# 1-Schematic_Bluetonium_canister.net
KiCad netlist of a schematic drawn in EasyEDA
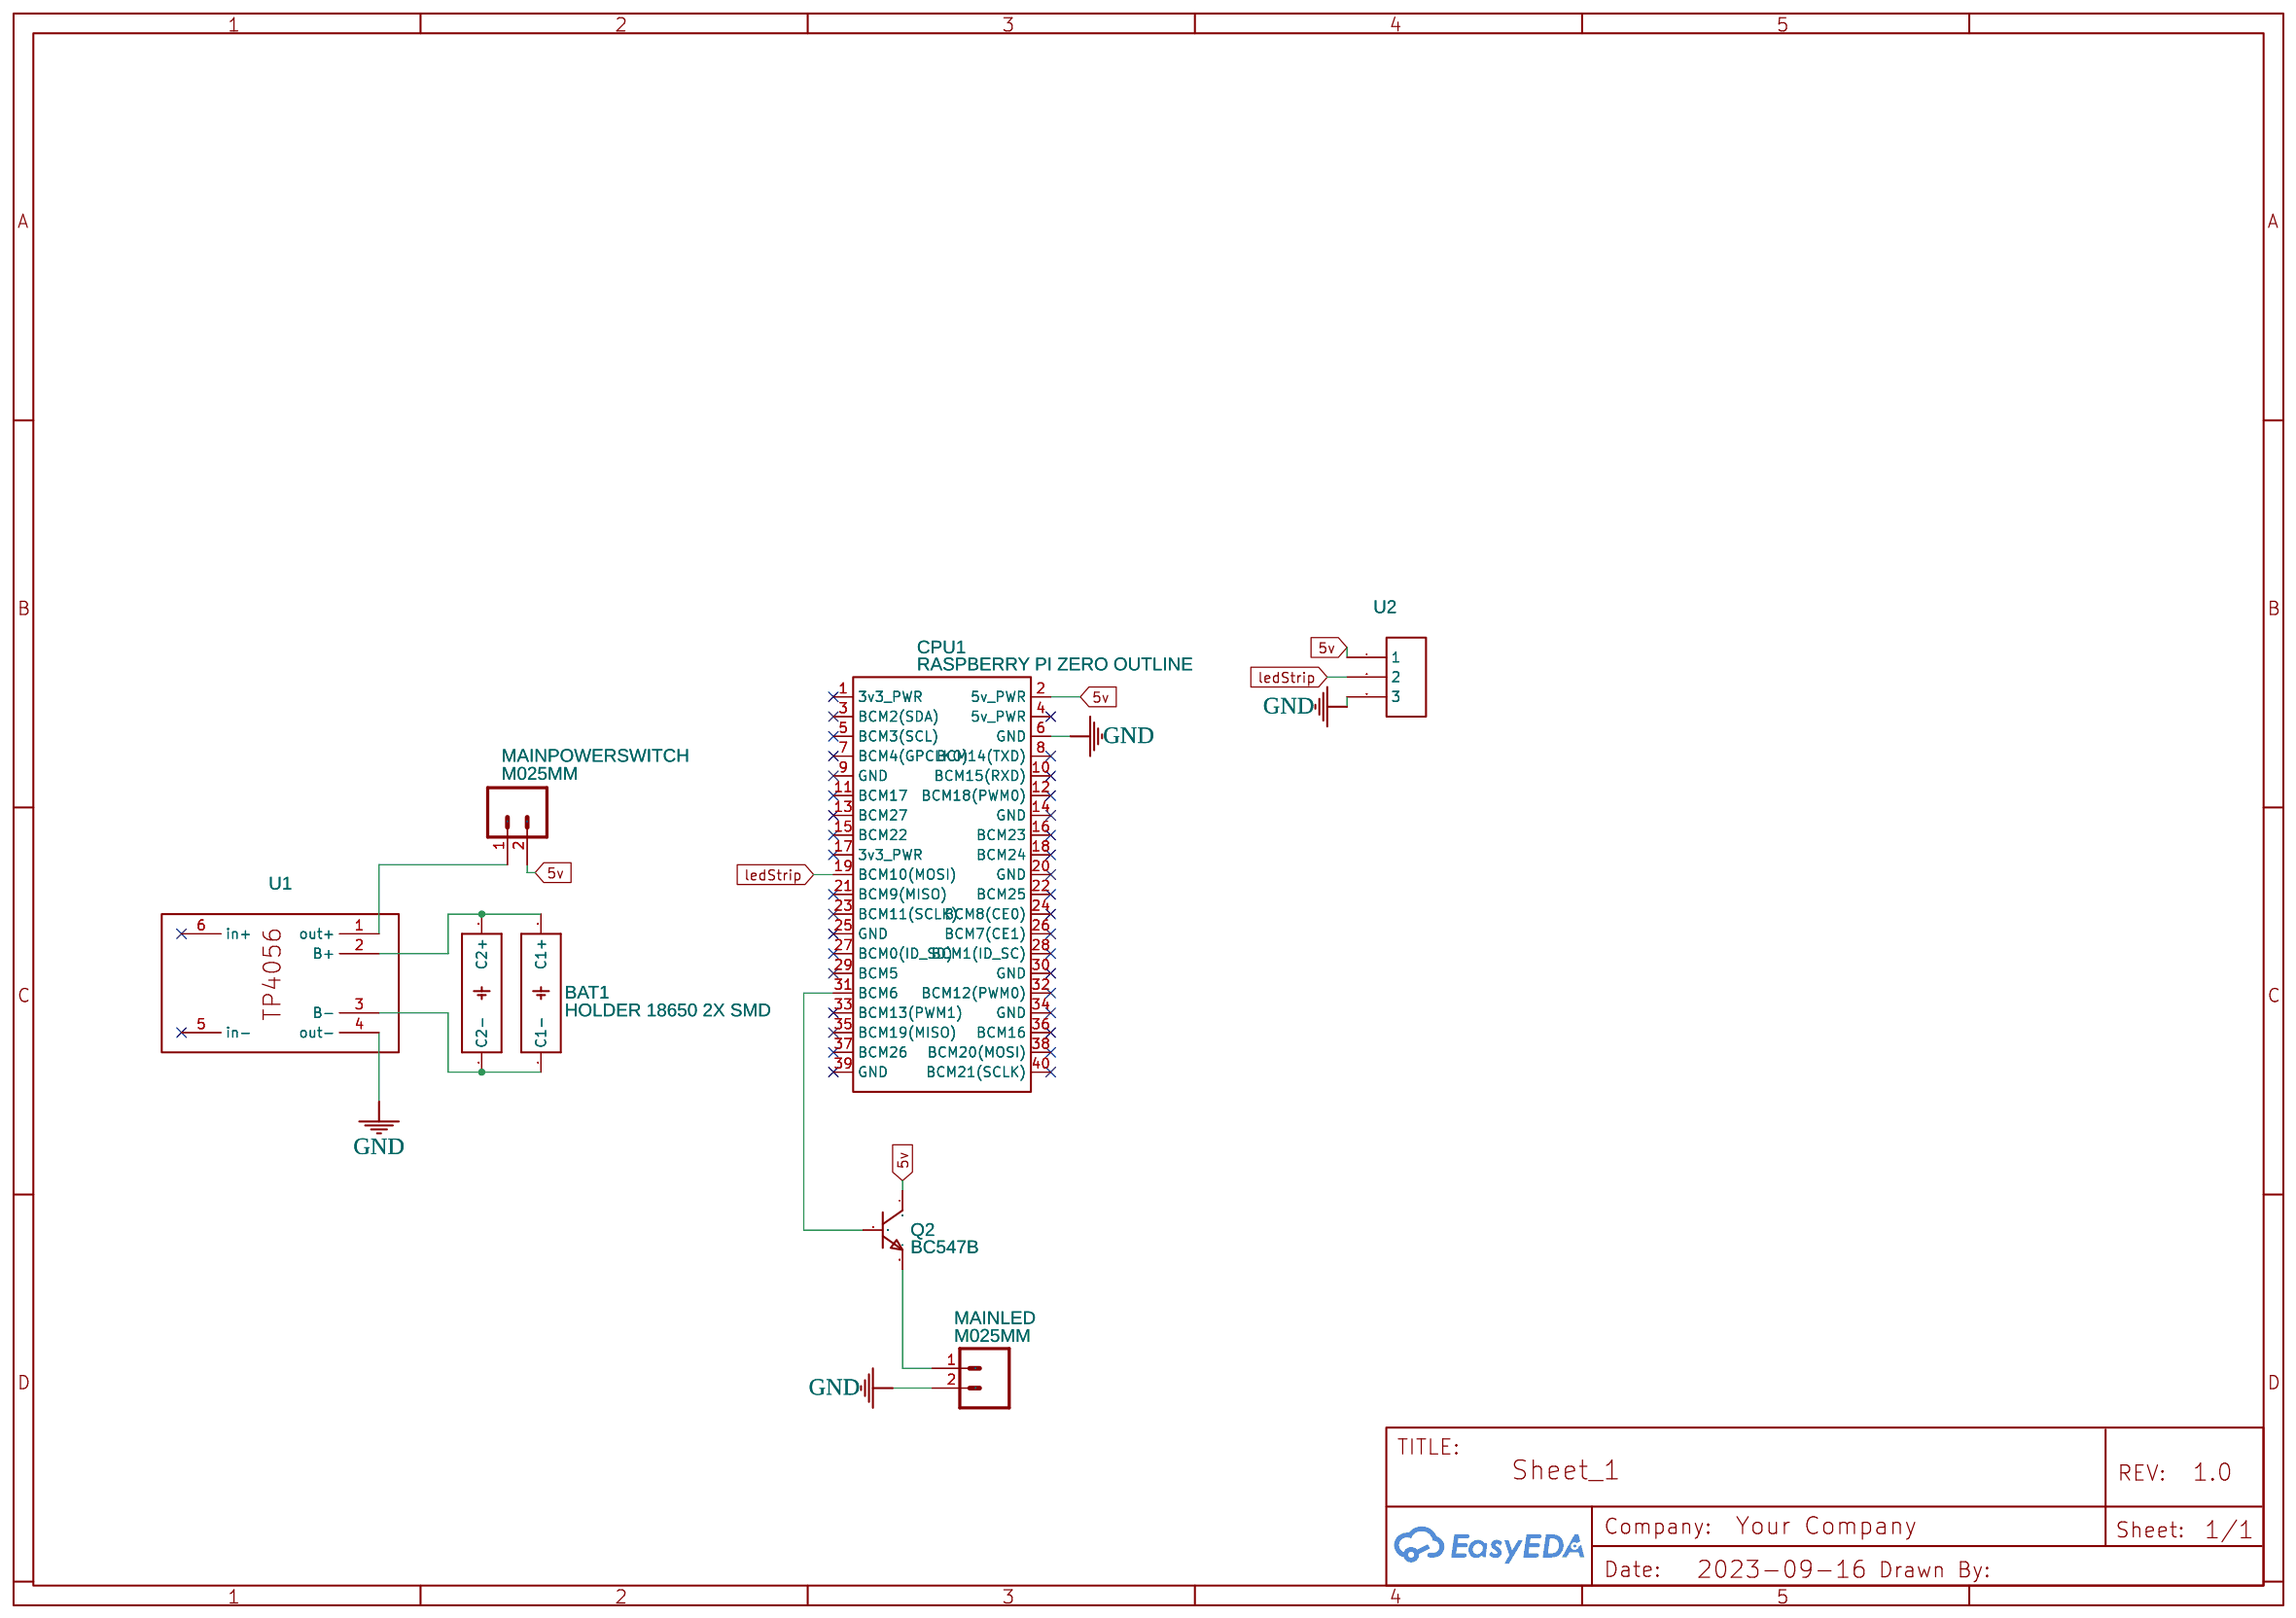
[diagram p0: schematic sheet]

(export (version "E")
  (design (tool "Eeschema 10.0.6"))
  (components
    (comp (ref "BAT1") (value "HOLDER 18650 2X SMD") (libsource (lib "") (part "HOLDER 18650 2X SMD")))
    (comp (ref "CPU1")
      (value "RASPBERRY PI ZERO OUTLINE")
      (fields (field (name "Manufacturer Part") "Pi Zero W") (field (name "Manufacturer") "Raspberry Pi"))
      (libsource (lib "") (part "RASPBERRY PI ZERO OUTLINE"))
    )
    (comp (ref "MAINLED") (value "M025MM") (libsource (lib "") (part "M025MM")))
    (comp (ref "MAINPOWERSWITCH") (value "M025MM") (libsource (lib "") (part "M025MM_1")))
    (comp (ref "Q2")
      (value "BC547B")
      (fields (field (name "Manufacturer") "MULTICOMP"))
      (libsource (lib "") (part "BC547B"))
    )
    (comp (ref "U1") (value "NO") (libsource (lib "") (part "TP4056")))
    (comp (ref "U2") (value "NO") (libsource (lib "") (part "PORT-3PIN-P2.54")))
  )
  (nets
    (net (code "1") (name "5v") (class "Default")
      (node (ref "CPU1") (pin "2") (pinfunction "5v_PWR_2") (pintype "unspecified"))
      (node (ref "MAINPOWERSWITCH") (pin "2") (pinfunction "2_2") (pintype "bidirectional"))
      (node (ref "Q2") (pin "1") (pinfunction "C_1") (pintype "unspecified"))
      (node (ref "U2") (pin "1") (pinfunction "1_1") (pintype "unspecified"))
    )
    (net (code "2") (name "GND") (class "Default")
      (node (ref "CPU1") (pin "6") (pinfunction "GND_6") (pintype "unspecified"))
      (node (ref "MAINLED") (pin "2") (pinfunction "2_2") (pintype "bidirectional"))
      (node (ref "U1") (pin "4") (pinfunction "out-_4") (pintype "unspecified"))
      (node (ref "U2") (pin "3") (pinfunction "3_3") (pintype "unspecified"))
    )
    (net (code "3") (name "Net-(BAT1-C1+)") (class "Default")
      (node (ref "BAT1") (pin "1+") (pinfunction "C1+_1+") (pintype "bidirectional"))
      (node (ref "BAT1") (pin "2+") (pinfunction "C2+_2+") (pintype "bidirectional"))
      (node (ref "U1") (pin "2") (pinfunction "B+_2") (pintype "unspecified"))
    )
    (net (code "4") (name "Net-(BAT1-C1-)") (class "Default")
      (node (ref "BAT1") (pin "1-") (pinfunction "C1-_1-") (pintype "bidirectional"))
      (node (ref "BAT1") (pin "2-") (pinfunction "C2-_2-") (pintype "bidirectional"))
      (node (ref "U1") (pin "3") (pinfunction "B-_3") (pintype "unspecified"))
    )
    (net (code "5") (name "Net-(CPU1-BCM6)") (class "Default")
      (node (ref "CPU1") (pin "31") (pinfunction "BCM6_31") (pintype "unspecified"))
      (node (ref "Q2") (pin "2") (pinfunction "B_2") (pintype "unspecified"))
    )
    (net (code "6") (name "Net-(Q2-E)") (class "Default")
      (node (ref "MAINLED") (pin "1") (pinfunction "1_1") (pintype "bidirectional"))
      (node (ref "Q2") (pin "3") (pinfunction "E_3") (pintype "unspecified"))
    )
    (net (code "7") (name "Net-(U1-out+)") (class "Default")
      (node (ref "MAINPOWERSWITCH") (pin "1") (pinfunction "1_1") (pintype "bidirectional"))
      (node (ref "U1") (pin "1") (pinfunction "out+_1") (pintype "unspecified"))
    )
    (net (code "8") (name "ledStrip") (class "Default")
      (node (ref "CPU1") (pin "19") (pinfunction "BCM10(MOSI)_19") (pintype "unspecified"))
      (node (ref "U2") (pin "2") (pinfunction "2_2") (pintype "unspecified"))
    )
    (net (code "9") (name "unconnected-(CPU1-3v3_PWR-Pad1)") (class "Default")
      (node (ref "CPU1") (pin "1") (pinfunction "3v3_PWR_1") (pintype "passive+no_connect"))
    )
    (net (code "10") (name "unconnected-(CPU1-3v3_PWR-Pad17)") (class "Default")
      (node (ref "CPU1") (pin "17") (pinfunction "3v3_PWR_17") (pintype "unspecified+no_connect"))
    )
    (net (code "11") (name "unconnected-(CPU1-5v_PWR-Pad4)") (class "Default")
      (node (ref "CPU1") (pin "4") (pinfunction "5v_PWR_4") (pintype "unspecified+no_connect"))
    )
    (net (code "12") (name "unconnected-(CPU1-BCM0(ID_SD)-Pad27)") (class "Default")
      (node (ref "CPU1") (pin "27") (pinfunction "BCM0(ID_SD)_27") (pintype "unspecified+no_connect"))
    )
    (net (code "13") (name "unconnected-(CPU1-BCM1(ID_SC)-Pad28)") (class "Default")
      (node (ref "CPU1") (pin "28") (pinfunction "BCM1(ID_SC)_28") (pintype "unspecified+no_connect"))
    )
    (net (code "14") (name "unconnected-(CPU1-BCM2(SDA)-Pad3)") (class "Default")
      (node (ref "CPU1") (pin "3") (pinfunction "BCM2(SDA)_3") (pintype "unspecified+no_connect"))
    )
    (net (code "15") (name "unconnected-(CPU1-BCM3(SCL)-Pad5)") (class "Default")
      (node (ref "CPU1") (pin "5") (pinfunction "BCM3(SCL)_5") (pintype "unspecified+no_connect"))
    )
    (net (code "16") (name "unconnected-(CPU1-BCM4(GPCLK0)-Pad7)") (class "Default")
      (node (ref "CPU1") (pin "7") (pinfunction "BCM4(GPCLK0)_7") (pintype "unspecified+no_connect"))
    )
    (net (code "17") (name "unconnected-(CPU1-BCM5-Pad29)") (class "Default")
      (node (ref "CPU1") (pin "29") (pinfunction "BCM5_29") (pintype "unspecified+no_connect"))
    )
    (net (code "18") (name "unconnected-(CPU1-BCM7(CE1)-Pad26)") (class "Default")
      (node (ref "CPU1") (pin "26") (pinfunction "BCM7(CE1)_26") (pintype "unspecified+no_connect"))
    )
    (net (code "19") (name "unconnected-(CPU1-BCM8(CE0)-Pad24)") (class "Default")
      (node (ref "CPU1") (pin "24") (pinfunction "BCM8(CE0)_24") (pintype "unspecified+no_connect"))
    )
    (net (code "20") (name "unconnected-(CPU1-BCM9(MISO)-Pad21)") (class "Default")
      (node (ref "CPU1") (pin "21") (pinfunction "BCM9(MISO)_21") (pintype "unspecified+no_connect"))
    )
    (net (code "21") (name "unconnected-(CPU1-BCM11(SCLK)-Pad23)") (class "Default")
      (node (ref "CPU1") (pin "23") (pinfunction "BCM11(SCLK)_23") (pintype "unspecified+no_connect"))
    )
    (net (code "22") (name "unconnected-(CPU1-BCM12(PWM0)-Pad32)") (class "Default")
      (node (ref "CPU1") (pin "32") (pinfunction "BCM12(PWM0)_32") (pintype "unspecified+no_connect"))
    )
    (net (code "23") (name "unconnected-(CPU1-BCM13(PWM1)-Pad33)") (class "Default")
      (node (ref "CPU1") (pin "33") (pinfunction "BCM13(PWM1)_33") (pintype "unspecified+no_connect"))
    )
    (net (code "24") (name "unconnected-(CPU1-BCM14(TXD)-Pad8)") (class "Default")
      (node (ref "CPU1") (pin "8") (pinfunction "BCM14(TXD)_8") (pintype "unspecified+no_connect"))
    )
    (net (code "25") (name "unconnected-(CPU1-BCM15(RXD)-Pad10)") (class "Default")
      (node (ref "CPU1") (pin "10") (pinfunction "BCM15(RXD)_10") (pintype "unspecified+no_connect"))
    )
    (net (code "26") (name "unconnected-(CPU1-BCM16-Pad36)") (class "Default")
      (node (ref "CPU1") (pin "36") (pinfunction "BCM16_36") (pintype "unspecified+no_connect"))
    )
    (net (code "27") (name "unconnected-(CPU1-BCM17-Pad11)") (class "Default")
      (node (ref "CPU1") (pin "11") (pinfunction "BCM17_11") (pintype "unspecified+no_connect"))
    )
    (net (code "28") (name "unconnected-(CPU1-BCM18(PWM0)-Pad12)") (class "Default")
      (node (ref "CPU1") (pin "12") (pinfunction "BCM18(PWM0)_12") (pintype "unspecified+no_connect"))
    )
    (net (code "29") (name "unconnected-(CPU1-BCM19(MISO)-Pad35)") (class "Default")
      (node (ref "CPU1") (pin "35") (pinfunction "BCM19(MISO)_35") (pintype "unspecified+no_connect"))
    )
    (net (code "30") (name "unconnected-(CPU1-BCM20(MOSI)-Pad38)") (class "Default")
      (node (ref "CPU1") (pin "38") (pinfunction "BCM20(MOSI)_38") (pintype "unspecified+no_connect"))
    )
    (net (code "31") (name "unconnected-(CPU1-BCM21(SCLK)-Pad40)") (class "Default")
      (node (ref "CPU1") (pin "40") (pinfunction "BCM21(SCLK)_40") (pintype "unspecified+no_connect"))
    )
    (net (code "32") (name "unconnected-(CPU1-BCM22-Pad15)") (class "Default")
      (node (ref "CPU1") (pin "15") (pinfunction "BCM22_15") (pintype "unspecified+no_connect"))
    )
    (net (code "33") (name "unconnected-(CPU1-BCM23-Pad16)") (class "Default")
      (node (ref "CPU1") (pin "16") (pinfunction "BCM23_16") (pintype "unspecified+no_connect"))
    )
    (net (code "34") (name "unconnected-(CPU1-BCM24-Pad18)") (class "Default")
      (node (ref "CPU1") (pin "18") (pinfunction "BCM24_18") (pintype "unspecified+no_connect"))
    )
    (net (code "35") (name "unconnected-(CPU1-BCM25-Pad22)") (class "Default")
      (node (ref "CPU1") (pin "22") (pinfunction "BCM25_22") (pintype "unspecified+no_connect"))
    )
    (net (code "36") (name "unconnected-(CPU1-BCM26-Pad37)") (class "Default")
      (node (ref "CPU1") (pin "37") (pinfunction "BCM26_37") (pintype "unspecified+no_connect"))
    )
    (net (code "37") (name "unconnected-(CPU1-BCM27-Pad13)") (class "Default")
      (node (ref "CPU1") (pin "13") (pinfunction "BCM27_13") (pintype "unspecified+no_connect"))
    )
    (net (code "38") (name "unconnected-(CPU1-GND-Pad9)") (class "Default")
      (node (ref "CPU1") (pin "9") (pinfunction "GND_9") (pintype "unspecified+no_connect"))
    )
    (net (code "39") (name "unconnected-(CPU1-GND-Pad14)") (class "Default")
      (node (ref "CPU1") (pin "14") (pinfunction "GND_14") (pintype "unspecified+no_connect"))
    )
    (net (code "40") (name "unconnected-(CPU1-GND-Pad20)") (class "Default")
      (node (ref "CPU1") (pin "20") (pinfunction "GND_20") (pintype "unspecified+no_connect"))
    )
    (net (code "41") (name "unconnected-(CPU1-GND-Pad25)") (class "Default")
      (node (ref "CPU1") (pin "25") (pinfunction "GND_25") (pintype "unspecified+no_connect"))
    )
    (net (code "42") (name "unconnected-(CPU1-GND-Pad30)") (class "Default")
      (node (ref "CPU1") (pin "30") (pinfunction "GND_30") (pintype "unspecified+no_connect"))
    )
    (net (code "43") (name "unconnected-(CPU1-GND-Pad34)") (class "Default")
      (node (ref "CPU1") (pin "34") (pinfunction "GND_34") (pintype "unspecified+no_connect"))
    )
    (net (code "44") (name "unconnected-(CPU1-GND-Pad39)") (class "Default")
      (node (ref "CPU1") (pin "39") (pinfunction "GND_39") (pintype "unspecified+no_connect"))
    )
    (net (code "45") (name "unconnected-(U1-in+-Pad6)") (class "Default")
      (node (ref "U1") (pin "6") (pinfunction "in+_6") (pintype "unspecified+no_connect"))
    )
    (net (code "46") (name "unconnected-(U1-in--Pad5)") (class "Default")
      (node (ref "U1") (pin "5") (pinfunction "in-_5") (pintype "unspecified+no_connect"))
    )
  )
)
